# ArduinoMicroFullCustom.net
KiCad netlist of a schematic drawn in EAGLE
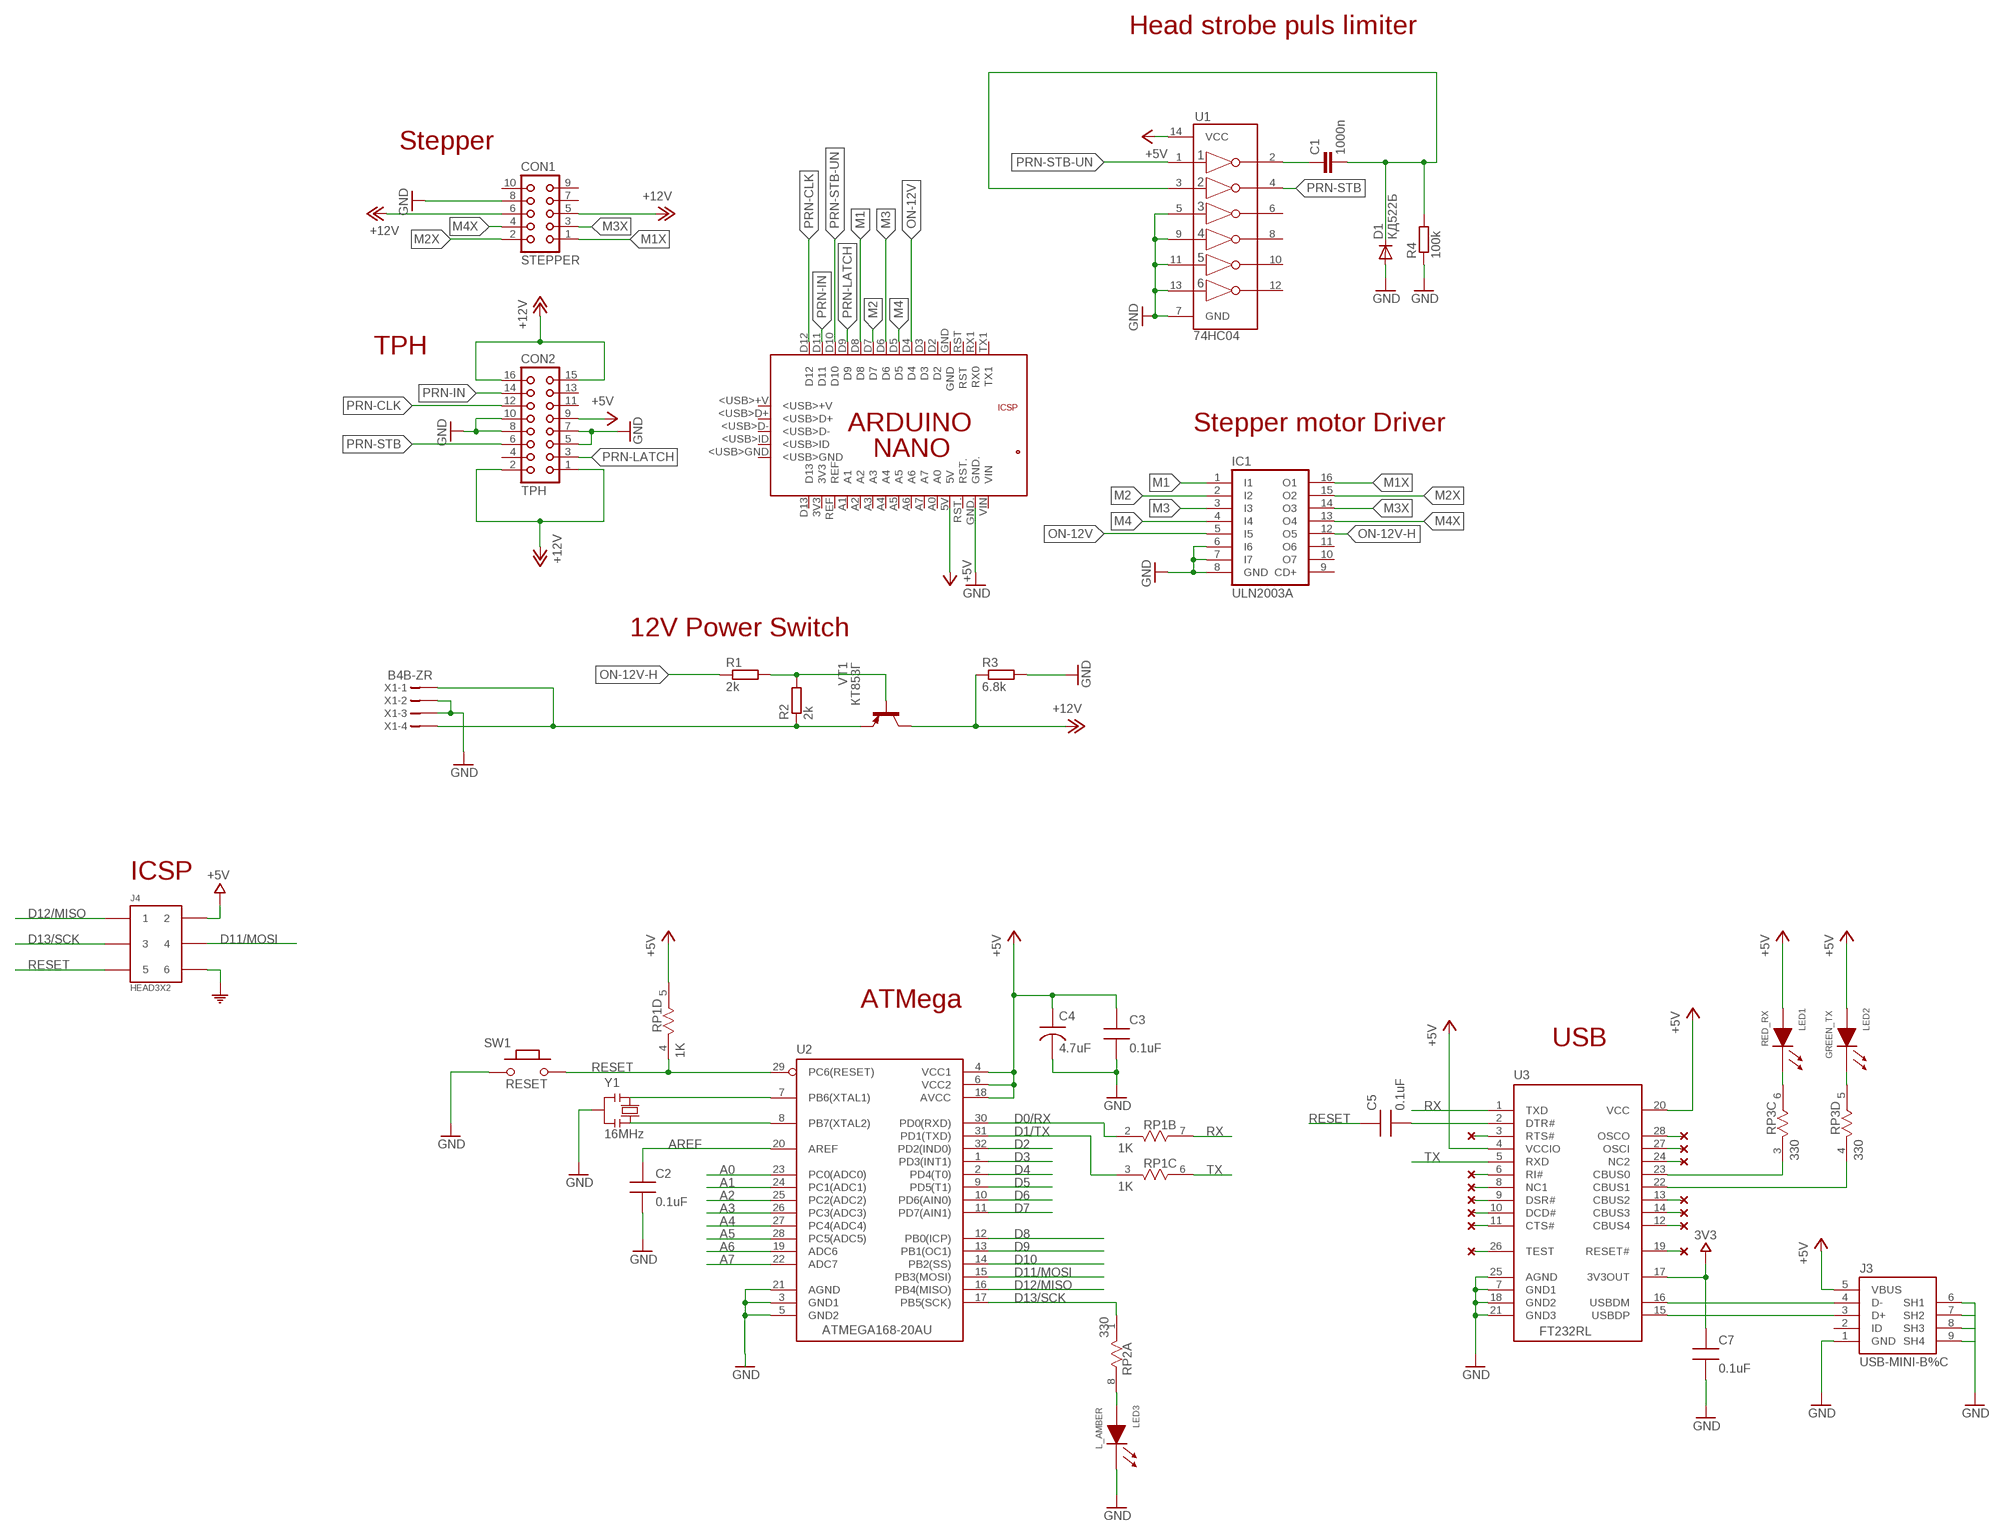
[diagram p0: schematic, sheet 1]

(export (version "E")
  (design (tool "Eeschema 10.0.6"))
  (components
    (comp (ref "C1")
      (value "1000n")
      (footprint "eagle-import:C075-032X103")
      (libsource (lib "eagle-import") (part "C-EU075-032X103"))
    )
    (comp (ref "C2")
      (value "0.1uF")
      (footprint "eagle-import:CAP0805-NP")
      (libsource (lib "eagle-import") (part "CAP0805-NP"))
    )
    (comp (ref "C3")
      (value "0.1uF")
      (footprint "eagle-import:CAP0805-NP")
      (libsource (lib "eagle-import") (part "CAP0805-NP"))
    )
    (comp (ref "C4")
      (value "4.7uF")
      (footprint "eagle-import:TAN-A")
      (libsource (lib "eagle-import") (part "CAP-TANA-P"))
    )
    (comp (ref "C5")
      (value "0.1uF")
      (footprint "eagle-import:CAP0805-NP")
      (libsource (lib "eagle-import") (part "CAP0805-NP"))
    )
    (comp (ref "C7")
      (value "0.1uF")
      (footprint "eagle-import:CAP0805-NP")
      (libsource (lib "eagle-import") (part "CAP0805-NP"))
    )
    (comp (ref "CON1")
      (value "STEPPER")
      (footprint "eagle-import:CON10")
      (fields
        (field (name "MF") "TE CONNECTIVITY / AMP")
        (field (name "MPN") "0-281273-1")
        (field (name "OC_FARNELL") "3816278")
      )
      (libsource (lib "eagle-import") (part "CON10"))
    )
    (comp (ref "CON2")
      (value "TPH")
      (footprint "eagle-import:CON16")
      (fields
        (field (name "MF") "TE CONNECTIVITY / AMP")
        (field (name "MPN") "1-1634688-0")
        (field (name "OC_FARNELL") "8395918")
      )
      (libsource (lib "eagle-import") (part "CON16"))
    )
    (comp (ref "D1")
      (value "КД522Б")
      (footprint "eagle-import:DO35-10")
      (libsource (lib "eagle-import") (part "1N4148DO35-10"))
    )
    (comp (ref "IC1")
      (value "ULN2003A")
      (footprint "eagle-import:DIL16")
      (libsource (lib "eagle-import") (part "ULN2003AN"))
    )
    (comp (ref "J3")
      (value "USB-MINI-B%C")
      (footprint "eagle-import:USB-MINI-B_2")
      (libsource (lib "eagle-import") (part "USB-MINI-B%C"))
    )
    (comp (ref "J4")
      (value "HEAD3X2")
      (footprint "eagle-import:HEAD3X2")
      (libsource (lib "eagle-import") (part "HEAD3X2"))
    )
    (comp (ref "LED1")
      (value "RED_RX")
      (footprint "eagle-import:LED0805")
      (libsource (lib "eagle-import") (part "LED0805"))
    )
    (comp (ref "LED2")
      (value "GREEN_TX")
      (footprint "eagle-import:LED0805")
      (libsource (lib "eagle-import") (part "LED0805"))
    )
    (comp (ref "LED3")
      (value "L_AMBER")
      (footprint "eagle-import:LED0805")
      (libsource (lib "eagle-import") (part "LED0805"))
    )
    (comp (ref "PCB1")
      (value "ARDUINO_NANO")
      (footprint "eagle-import:ARDUINO_NANO")
      (fields (field (name "MF") "ARDUINO") (field (name "MPN") "A000005"))
      (libsource (lib "eagle-import") (part "ARDUINO_NANO"))
    )
    (comp (ref "R1")
      (value "2k")
      (footprint "eagle-import:0207_12")
      (libsource (lib "eagle-import") (part "R-EU_0207/12"))
    )
    (comp (ref "R2")
      (value "2k")
      (footprint "eagle-import:0207_12")
      (libsource (lib "eagle-import") (part "R-EU_0207/12"))
    )
    (comp (ref "R3")
      (value "6.8k")
      (footprint "eagle-import:0207_12")
      (libsource (lib "eagle-import") (part "R-EU_0207/12"))
    )
    (comp (ref "R4")
      (value "100k")
      (footprint "eagle-import:0309_12")
      (libsource (lib "eagle-import") (part "R-EU_0309/12"))
    )
    (comp (ref "RP1")
      (value "1K")
      (footprint "eagle-import:RES4NT")
      (libsource (lib "eagle-import") (part "RES4NT"))
    )
    (comp (ref "RP2")
      (value "330")
      (footprint "eagle-import:RES4NT")
      (libsource (lib "eagle-import") (part "RES4NT"))
    )
    (comp (ref "RP3")
      (value "330")
      (footprint "eagle-import:RES4NT")
      (libsource (lib "eagle-import") (part "RES4NT"))
    )
    (comp (ref "SW1")
      (value "RESET")
      (footprint "eagle-import:157SW")
      (libsource (lib "eagle-import") (part "PB157"))
    )
    (comp (ref "U1")
      (value "74HC04")
      (footprint "eagle-import:DIL14")
      (libsource (lib "eagle-import") (part "74HC04_HEX_INVERTER"))
    )
    (comp (ref "U2")
      (value "ATMEGA168-20AU")
      (footprint "eagle-import:QFP032")
      (libsource (lib "eagle-import") (part "ATMEGA168-20AU"))
    )
    (comp (ref "U3")
      (value "FT232RL")
      (footprint "eagle-import:SSOP28")
      (libsource (lib "eagle-import") (part "FT232RL"))
    )
    (comp (ref "VT1")
      (value "КТ853Г")
      (footprint "eagle-import:TO220")
      (libsource (lib "eagle-import") (part "TIP30"))
    )
    (comp (ref "X1")
      (value "B4B-ZR")
      (footprint "eagle-import:B4B-ZR")
      (fields (field (name "MF") "FARNELL") (field (name "MPN") "B4B-ZR(LF)(SN)"))
      (libsource (lib "eagle-import") (part "?4B-ZRB"))
    )
    (comp (ref "Y1")
      (value "16MHz")
      (footprint "eagle-import:RESONATOR")
      (libsource (lib "eagle-import") (part "RESONATORMU"))
    )
  )
  (nets
    (net (code "1") (name "+5V") (class "Default")
      (node (ref "C3") (pin "1") (pinfunction "1_1") (pintype "passive"))
      (node (ref "C4") (pin "1") (pinfunction "1_1") (pintype "passive"))
      (node (ref "CON2") (pin "9") (pinfunction "9_9") (pintype "passive"))
      (node (ref "J3") (pin "5") (pinfunction "VBUS_5") (pintype "power_in"))
      (node (ref "J4") (pin "2") (pinfunction "2_2") (pintype "passive"))
      (node (ref "LED1") (pin "2") (pinfunction "AN_2") (pintype "passive"))
      (node (ref "LED2") (pin "2") (pinfunction "AN_2") (pintype "passive"))
      (node (ref "PCB1") (pin "5V") (pinfunction "5V_5V") (pintype "bidirectional"))
      (node (ref "RP1") (pin "5") (pinfunction "2_5") (pintype "passive"))
      (node (ref "U1") (pin "14") (pinfunction "VCC_14") (pintype "power_in"))
      (node (ref "U2") (pin "18") (pinfunction "AVCC_18") (pintype "passive"))
      (node (ref "U2") (pin "4") (pinfunction "VCC1_4") (pintype "power_in"))
      (node (ref "U2") (pin "6") (pinfunction "VCC2_6") (pintype "power_in"))
      (node (ref "U3") (pin "20") (pinfunction "VCC_20") (pintype "power_in"))
      (node (ref "U3") (pin "4") (pinfunction "VCCIO_4") (pintype "power_in"))
    )
    (net (code "2") (name "+12V") (class "Default")
      (node (ref "CON1") (pin "5") (pinfunction "5_5") (pintype "passive"))
      (node (ref "CON1") (pin "6") (pinfunction "6_6") (pintype "passive"))
      (node (ref "CON2") (pin "1") (pinfunction "1_1") (pintype "passive"))
      (node (ref "CON2") (pin "15") (pinfunction "15_15") (pintype "passive"))
      (node (ref "CON2") (pin "16") (pinfunction "16_16") (pintype "passive"))
      (node (ref "CON2") (pin "2") (pinfunction "2_2") (pintype "passive"))
      (node (ref "R3") (pin "1") (pinfunction "1_1") (pintype "passive"))
      (node (ref "VT1") (pin "2") (pinfunction "C_2") (pintype "passive"))
    )
    (net (code "3") (name "/A0") (class "Default")
      (node (ref "U2") (pin "23") (pinfunction "PC0(ADC0)_23") (pintype "passive"))
    )
    (net (code "4") (name "/A1") (class "Default")
      (node (ref "U2") (pin "24") (pinfunction "PC1(ADC1)_24") (pintype "passive"))
    )
    (net (code "5") (name "/A2") (class "Default")
      (node (ref "U2") (pin "25") (pinfunction "PC2(ADC2)_25") (pintype "passive"))
    )
    (net (code "6") (name "/A3") (class "Default")
      (node (ref "U2") (pin "26") (pinfunction "PC3(ADC3)_26") (pintype "passive"))
    )
    (net (code "7") (name "/A4") (class "Default")
      (node (ref "U2") (pin "27") (pinfunction "PC4(ADC4)_27") (pintype "passive"))
    )
    (net (code "8") (name "/A5") (class "Default")
      (node (ref "U2") (pin "28") (pinfunction "PC5(ADC5)_28") (pintype "passive"))
    )
    (net (code "9") (name "/A6") (class "Default")
      (node (ref "U2") (pin "19") (pinfunction "ADC6_19") (pintype "passive"))
    )
    (net (code "10") (name "/A7") (class "Default")
      (node (ref "U2") (pin "22") (pinfunction "ADC7_22") (pintype "passive"))
    )
    (net (code "11") (name "/AREF") (class "Default")
      (node (ref "C2") (pin "1") (pinfunction "1_1") (pintype "passive"))
      (node (ref "U2") (pin "20") (pinfunction "AREF_20") (pintype "passive"))
    )
    (net (code "12") (name "/D0{slash}RX") (class "Default")
      (node (ref "RP1") (pin "2") (pinfunction "1_2") (pintype "passive"))
      (node (ref "U2") (pin "30") (pinfunction "PD0(RXD)_30") (pintype "bidirectional"))
    )
    (net (code "13") (name "/D1{slash}TX") (class "Default")
      (node (ref "RP1") (pin "3") (pinfunction "1_3") (pintype "passive"))
      (node (ref "U2") (pin "31") (pinfunction "PD1(TXD)_31") (pintype "bidirectional"))
    )
    (net (code "14") (name "/D2") (class "Default")
      (node (ref "U2") (pin "32") (pinfunction "PD2(IND0)_32") (pintype "bidirectional"))
    )
    (net (code "15") (name "/D3") (class "Default")
      (node (ref "U2") (pin "1") (pinfunction "PD3(INT1)_1") (pintype "bidirectional"))
    )
    (net (code "16") (name "/D4") (class "Default")
      (node (ref "U2") (pin "2") (pinfunction "PD4(T0)_2") (pintype "bidirectional"))
    )
    (net (code "17") (name "/D5") (class "Default")
      (node (ref "U2") (pin "9") (pinfunction "PD5(T1)_9") (pintype "bidirectional"))
    )
    (net (code "18") (name "/D6") (class "Default")
      (node (ref "U2") (pin "10") (pinfunction "PD6(AIN0)_10") (pintype "bidirectional"))
    )
    (net (code "19") (name "/D7") (class "Default")
      (node (ref "U2") (pin "11") (pinfunction "PD7(AIN1)_11") (pintype "bidirectional"))
    )
    (net (code "20") (name "/D8") (class "Default")
      (node (ref "U2") (pin "12") (pinfunction "PB0(ICP)_12") (pintype "bidirectional"))
    )
    (net (code "21") (name "/D9") (class "Default")
      (node (ref "U2") (pin "13") (pinfunction "PB1(OC1)_13") (pintype "bidirectional"))
    )
    (net (code "22") (name "/D10") (class "Default")
      (node (ref "U2") (pin "14") (pinfunction "PB2(SS)_14") (pintype "bidirectional"))
    )
    (net (code "23") (name "/D11{slash}MOSI") (class "Default")
      (node (ref "J4") (pin "4") (pinfunction "4_4") (pintype "passive"))
      (node (ref "U2") (pin "15") (pinfunction "PB3(MOSI)_15") (pintype "bidirectional"))
    )
    (net (code "24") (name "/D12{slash}MISO") (class "Default")
      (node (ref "J4") (pin "1") (pinfunction "1_1") (pintype "passive"))
      (node (ref "U2") (pin "16") (pinfunction "PB4(MISO)_16") (pintype "bidirectional"))
    )
    (net (code "25") (name "/D13{slash}SCK") (class "Default")
      (node (ref "J4") (pin "3") (pinfunction "3_3") (pintype "passive"))
      (node (ref "RP2") (pin "1") (pinfunction "1_1") (pintype "passive"))
      (node (ref "U2") (pin "17") (pinfunction "PB5(SCK)_17") (pintype "bidirectional"))
    )
    (net (code "26") (name "/RESET") (class "Default")
      (node (ref "C5") (pin "1") (pinfunction "1_1") (pintype "passive"))
      (node (ref "J4") (pin "5") (pinfunction "5_5") (pintype "passive"))
      (node (ref "RP1") (pin "4") (pinfunction "1_4") (pintype "passive"))
      (node (ref "SW1") (pin "2") (pinfunction "2_2") (pintype "passive"))
      (node (ref "U2") (pin "29") (pinfunction "PC6(RESET)_29") (pintype "bidirectional"))
    )
    (net (code "27") (name "/RX") (class "Default")
      (node (ref "RP1") (pin "7") (pinfunction "2_7") (pintype "passive"))
      (node (ref "U3") (pin "1") (pinfunction "TXD_1") (pintype "output"))
    )
    (net (code "28") (name "/TX") (class "Default")
      (node (ref "RP1") (pin "6") (pinfunction "2_6") (pintype "passive"))
      (node (ref "U3") (pin "5") (pinfunction "RXD_5") (pintype "input"))
    )
    (net (code "29") (name "3V3") (class "Default")
      (node (ref "C7") (pin "1") (pinfunction "1_1") (pintype "passive"))
      (node (ref "U3") (pin "17") (pinfunction "3V3OUT_17") (pintype "power_in"))
    )
    (net (code "30") (name "COM") (class "Default")
      (node (ref "J4") (pin "6") (pinfunction "6_6") (pintype "passive"))
    )
    (net (code "31") (name "GND") (class "Default")
      (node (ref "C2") (pin "2") (pinfunction "2_2") (pintype "passive"))
      (node (ref "C3") (pin "2") (pinfunction "2_2") (pintype "passive"))
      (node (ref "C4") (pin "2") (pinfunction "2_2") (pintype "passive"))
      (node (ref "C7") (pin "2") (pinfunction "2_2") (pintype "passive"))
      (node (ref "CON1") (pin "8") (pinfunction "8_8") (pintype "passive"))
      (node (ref "CON2") (pin "10") (pinfunction "10_10") (pintype "passive"))
      (node (ref "CON2") (pin "5") (pinfunction "5_5") (pintype "passive"))
      (node (ref "CON2") (pin "7") (pinfunction "7_7") (pintype "passive"))
      (node (ref "CON2") (pin "8") (pinfunction "8_8") (pintype "passive"))
      (node (ref "D1") (pin "A") (pinfunction "A_A") (pintype "passive"))
      (node (ref "IC1") (pin "6") (pinfunction "I6_6") (pintype "input"))
      (node (ref "IC1") (pin "7") (pinfunction "I7_7") (pintype "input"))
      (node (ref "IC1") (pin "8") (pinfunction "GND_8") (pintype "power_in"))
      (node (ref "J3") (pin "1") (pinfunction "GND_1") (pintype "passive"))
      (node (ref "J3") (pin "6") (pinfunction "SH1_6") (pintype "passive"))
      (node (ref "J3") (pin "7") (pinfunction "SH2_7") (pintype "passive"))
      (node (ref "J3") (pin "8") (pinfunction "SH3_8") (pintype "passive"))
      (node (ref "J3") (pin "9") (pinfunction "SH4_9") (pintype "passive"))
      (node (ref "LED3") (pin "1") (pinfunction "CA_1") (pintype "passive"))
      (node (ref "PCB1") (pin "GND.") (pinfunction "GND._GND.") (pintype "bidirectional"))
      (node (ref "R3") (pin "2") (pinfunction "2_2") (pintype "passive"))
      (node (ref "R4") (pin "1") (pinfunction "1_1") (pintype "passive"))
      (node (ref "SW1") (pin "1") (pinfunction "1_1") (pintype "passive"))
      (node (ref "U1") (pin "11") (pinfunction "5A_11") (pintype "input"))
      (node (ref "U1") (pin "13") (pinfunction "6A_13") (pintype "input"))
      (node (ref "U1") (pin "5") (pinfunction "3A_5") (pintype "input"))
      (node (ref "U1") (pin "7") (pinfunction "GND_7") (pintype "power_in"))
      (node (ref "U1") (pin "9") (pinfunction "4A_9") (pintype "input"))
      (node (ref "U2") (pin "21") (pinfunction "AGND_21") (pintype "passive"))
      (node (ref "U2") (pin "3") (pinfunction "GND1_3") (pintype "power_in"))
      (node (ref "U2") (pin "5") (pinfunction "GND2_5") (pintype "power_in"))
      (node (ref "U3") (pin "18") (pinfunction "GND2_18") (pintype "power_in"))
      (node (ref "U3") (pin "21") (pinfunction "GND3_21") (pintype "power_in"))
      (node (ref "U3") (pin "25") (pinfunction "AGND_25") (pintype "power_in"))
      (node (ref "U3") (pin "7") (pinfunction "GND1_7") (pintype "power_in"))
      (node (ref "X1") (pin "2") (pinfunction "1_2") (pintype "passive"))
      (node (ref "X1") (pin "3") (pinfunction "1_3") (pintype "passive"))
      (node (ref "Y1") (pin "2") (pinfunction "2_2") (pintype "passive"))
    )
    (net (code "32") (name "M1") (class "Default")
      (node (ref "IC1") (pin "1") (pinfunction "I1_1") (pintype "input"))
      (node (ref "PCB1") (pin "D8") (pinfunction "D8_D8") (pintype "bidirectional"))
    )
    (net (code "33") (name "M1X") (class "Default")
      (node (ref "CON1") (pin "1") (pinfunction "1_1") (pintype "passive"))
      (node (ref "IC1") (pin "16") (pinfunction "O1_16") (pintype "open_collector"))
    )
    (net (code "34") (name "M2") (class "Default")
      (node (ref "IC1") (pin "2") (pinfunction "I2_2") (pintype "input"))
      (node (ref "PCB1") (pin "D7") (pinfunction "D7_D7") (pintype "bidirectional"))
    )
    (net (code "35") (name "M2X") (class "Default")
      (node (ref "CON1") (pin "2") (pinfunction "2_2") (pintype "passive"))
      (node (ref "IC1") (pin "15") (pinfunction "O2_15") (pintype "open_collector"))
    )
    (net (code "36") (name "M3") (class "Default")
      (node (ref "IC1") (pin "3") (pinfunction "I3_3") (pintype "input"))
      (node (ref "PCB1") (pin "D6") (pinfunction "D6_D6") (pintype "bidirectional"))
    )
    (net (code "37") (name "M3X") (class "Default")
      (node (ref "CON1") (pin "3") (pinfunction "3_3") (pintype "passive"))
      (node (ref "IC1") (pin "14") (pinfunction "O3_14") (pintype "open_collector"))
    )
    (net (code "38") (name "M4") (class "Default")
      (node (ref "IC1") (pin "4") (pinfunction "I4_4") (pintype "input"))
      (node (ref "PCB1") (pin "D5") (pinfunction "D5_D5") (pintype "bidirectional"))
    )
    (net (code "39") (name "M4X") (class "Default")
      (node (ref "CON1") (pin "4") (pinfunction "4_4") (pintype "passive"))
      (node (ref "IC1") (pin "13") (pinfunction "O4_13") (pintype "open_collector"))
    )
    (net (code "40") (name "Net-(J3-D+)") (class "Default")
      (node (ref "J3") (pin "3") (pinfunction "D+_3") (pintype "bidirectional"))
      (node (ref "U3") (pin "15") (pinfunction "USBDP_15") (pintype "bidirectional"))
    )
    (net (code "41") (name "Net-(J3-D-)") (class "Default")
      (node (ref "J3") (pin "4") (pinfunction "D-_4") (pintype "bidirectional"))
      (node (ref "U3") (pin "16") (pinfunction "USBDM_16") (pintype "bidirectional"))
    )
    (net (code "42") (name "Net-(LED1-CA)") (class "Default")
      (node (ref "LED1") (pin "1") (pinfunction "CA_1") (pintype "passive"))
      (node (ref "RP3") (pin "6") (pinfunction "2_6") (pintype "passive"))
    )
    (net (code "43") (name "Net-(LED2-CA)") (class "Default")
      (node (ref "LED2") (pin "1") (pinfunction "CA_1") (pintype "passive"))
      (node (ref "RP3") (pin "5") (pinfunction "2_5") (pintype "passive"))
    )
    (net (code "44") (name "Net-(LED3-AN)") (class "Default")
      (node (ref "LED3") (pin "2") (pinfunction "AN_2") (pintype "passive"))
      (node (ref "RP2") (pin "8") (pinfunction "2_8") (pintype "passive"))
    )
    (net (code "45") (name "Net-(RP3C-1)") (class "Default")
      (node (ref "RP3") (pin "3") (pinfunction "1_3") (pintype "passive"))
      (node (ref "U3") (pin "23") (pinfunction "CBUS0_23") (pintype "bidirectional"))
    )
    (net (code "46") (name "Net-(RP3D-1)") (class "Default")
      (node (ref "RP3") (pin "4") (pinfunction "1_4") (pintype "passive"))
      (node (ref "U3") (pin "22") (pinfunction "CBUS1_22") (pintype "bidirectional"))
    )
    (net (code "47") (name "Net-(U1-1Y)") (class "Default")
      (node (ref "C1") (pin "1") (pinfunction "1_1") (pintype "passive"))
      (node (ref "U1") (pin "2") (pinfunction "1Y_2") (pintype "output"))
    )
    (net (code "48") (name "Net-(U1-2A)") (class "Default")
      (node (ref "C1") (pin "2") (pinfunction "2_2") (pintype "passive"))
      (node (ref "D1") (pin "C") (pinfunction "C_C") (pintype "passive"))
      (node (ref "R4") (pin "2") (pinfunction "2_2") (pintype "passive"))
      (node (ref "U1") (pin "3") (pinfunction "2A_3") (pintype "input"))
    )
    (net (code "49") (name "Net-(U2-PB6(XTAL1))") (class "Default")
      (node (ref "U2") (pin "7") (pinfunction "PB6(XTAL1)_7") (pintype "passive"))
      (node (ref "Y1") (pin "1") (pinfunction "1_1") (pintype "passive"))
    )
    (net (code "50") (name "Net-(U2-PB7(XTAL2))") (class "Default")
      (node (ref "U2") (pin "8") (pinfunction "PB7(XTAL2)_8") (pintype "passive"))
      (node (ref "Y1") (pin "3") (pinfunction "3_3") (pintype "passive"))
    )
    (net (code "51") (name "Net-(U3-DTR#)") (class "Default")
      (node (ref "C5") (pin "2") (pinfunction "2_2") (pintype "passive"))
      (node (ref "U3") (pin "2") (pinfunction "DTR#_2") (pintype "output"))
    )
    (net (code "52") (name "Net-(VT1-B)") (class "Default")
      (node (ref "R1") (pin "2") (pinfunction "2_2") (pintype "passive"))
      (node (ref "R2") (pin "2") (pinfunction "2_2") (pintype "passive"))
      (node (ref "VT1") (pin "1") (pinfunction "B_1") (pintype "passive"))
    )
    (net (code "53") (name "Net-(VT1-E)") (class "Default")
      (node (ref "R2") (pin "1") (pinfunction "1_1") (pintype "passive"))
      (node (ref "VT1") (pin "3") (pinfunction "E_3") (pintype "passive"))
      (node (ref "X1") (pin "1") (pinfunction "1_1") (pintype "passive"))
      (node (ref "X1") (pin "4") (pinfunction "1_4") (pintype "passive"))
    )
    (net (code "54") (name "ON-12V") (class "Default")
      (node (ref "IC1") (pin "5") (pinfunction "I5_5") (pintype "input"))
      (node (ref "PCB1") (pin "D4") (pinfunction "D4_D4") (pintype "bidirectional"))
    )
    (net (code "55") (name "ON-12V-H") (class "Default")
      (node (ref "IC1") (pin "12") (pinfunction "O5_12") (pintype "open_collector"))
      (node (ref "R1") (pin "1") (pinfunction "1_1") (pintype "passive"))
    )
    (net (code "56") (name "PRN-CLK") (class "Default")
      (node (ref "CON2") (pin "12") (pinfunction "12_12") (pintype "passive"))
      (node (ref "PCB1") (pin "D12") (pinfunction "D12_D12") (pintype "bidirectional"))
    )
    (net (code "57") (name "PRN-IN") (class "Default")
      (node (ref "CON2") (pin "14") (pinfunction "14_14") (pintype "passive"))
      (node (ref "PCB1") (pin "D11") (pinfunction "D11_D11") (pintype "bidirectional"))
    )
    (net (code "58") (name "PRN-LATCH") (class "Default")
      (node (ref "CON2") (pin "3") (pinfunction "3_3") (pintype "passive"))
      (node (ref "PCB1") (pin "D9") (pinfunction "D9_D9") (pintype "bidirectional"))
    )
    (net (code "59") (name "PRN-STB") (class "Default")
      (node (ref "CON2") (pin "6") (pinfunction "6_6") (pintype "passive"))
      (node (ref "U1") (pin "4") (pinfunction "2Y_4") (pintype "output"))
    )
    (net (code "60") (name "PRN-STB-UN") (class "Default")
      (node (ref "PCB1") (pin "D10") (pinfunction "D10_D10") (pintype "bidirectional"))
      (node (ref "U1") (pin "1") (pinfunction "1A_1") (pintype "input"))
    )
    (net (code "61") (name "unconnected-(CON1-Pad7)") (class "Default")
      (node (ref "CON1") (pin "7") (pinfunction "7_7") (pintype "passive"))
    )
    (net (code "62") (name "unconnected-(CON1-Pad9)") (class "Default")
      (node (ref "CON1") (pin "9") (pinfunction "9_9") (pintype "passive"))
    )
    (net (code "63") (name "unconnected-(CON1-Pad10)") (class "Default")
      (node (ref "CON1") (pin "10") (pinfunction "10_10") (pintype "passive"))
    )
    (net (code "64") (name "unconnected-(CON2-Pad4)") (class "Default")
      (node (ref "CON2") (pin "4") (pinfunction "4_4") (pintype "passive"))
    )
    (net (code "65") (name "unconnected-(CON2-Pad11)") (class "Default")
      (node (ref "CON2") (pin "11") (pinfunction "11_11") (pintype "passive"))
    )
    (net (code "66") (name "unconnected-(CON2-Pad13)") (class "Default")
      (node (ref "CON2") (pin "13") (pinfunction "13_13") (pintype "passive"))
    )
    (net (code "67") (name "unconnected-(IC1-CD+-Pad9)") (class "Default")
      (node (ref "IC1") (pin "9") (pinfunction "CD+_9") (pintype "passive"))
    )
    (net (code "68") (name "unconnected-(IC1-O6-Pad11)") (class "Default")
      (node (ref "IC1") (pin "11") (pinfunction "O6_11") (pintype "open_collector"))
    )
    (net (code "69") (name "unconnected-(IC1-O7-Pad10)") (class "Default")
      (node (ref "IC1") (pin "10") (pinfunction "O7_10") (pintype "open_collector"))
    )
    (net (code "70") (name "unconnected-(J3-ID-Pad2)") (class "Default")
      (node (ref "J3") (pin "2") (pinfunction "ID_2") (pintype "bidirectional"))
    )
    (net (code "71") (name "unconnected-(PCB1-Pad3V3)") (class "Default")
      (node (ref "PCB1") (pin "3V3") (pinfunction "3V3_3V3") (pintype "bidirectional"))
    )
    (net (code "72") (name "unconnected-(PCB1-Pad5V.)") (class "Default")
      (node (ref "PCB1") (pin "5V.") (pinfunction "5V._5V.") (pintype "bidirectional"))
    )
    (net (code "73") (name "unconnected-(PCB1-Pad<USB>+V)") (class "Default")
      (node (ref "PCB1") (pin "<USB>+V") (pinfunction "<USB>+V_<USB>+V") (pintype "bidirectional"))
    )
    (net (code "74") (name "unconnected-(PCB1-Pad<USB>D+)") (class "Default")
      (node (ref "PCB1") (pin "<USB>D+") (pinfunction "<USB>D+_<USB>D+") (pintype "bidirectional"))
    )
    (net (code "75") (name "unconnected-(PCB1-Pad<USB>D-)") (class "Default")
      (node (ref "PCB1") (pin "<USB>D-") (pinfunction "<USB>D-_<USB>D-") (pintype "bidirectional"))
    )
    (net (code "76") (name "unconnected-(PCB1-Pad<USB>GND)") (class "Default")
      (node (ref "PCB1") (pin "<USB>GND") (pinfunction "<USB>GND_<USB>GND") (pintype "bidirectional"))
    )
    (net (code "77") (name "unconnected-(PCB1-Pad<USB>ID)") (class "Default")
      (node (ref "PCB1") (pin "<USB>ID") (pinfunction "<USB>ID_<USB>ID") (pintype "bidirectional"))
    )
    (net (code "78") (name "unconnected-(PCB1-PadA0)") (class "Default")
      (node (ref "PCB1") (pin "A0") (pinfunction "A0_A0") (pintype "bidirectional"))
    )
    (net (code "79") (name "unconnected-(PCB1-PadA1)") (class "Default")
      (node (ref "PCB1") (pin "A1") (pinfunction "A1_A1") (pintype "bidirectional"))
    )
    (net (code "80") (name "unconnected-(PCB1-PadA2)") (class "Default")
      (node (ref "PCB1") (pin "A2") (pinfunction "A2_A2") (pintype "bidirectional"))
    )
    (net (code "81") (name "unconnected-(PCB1-PadA3)") (class "Default")
      (node (ref "PCB1") (pin "A3") (pinfunction "A3_A3") (pintype "bidirectional"))
    )
    (net (code "82") (name "unconnected-(PCB1-PadA4)") (class "Default")
      (node (ref "PCB1") (pin "A4") (pinfunction "A4_A4") (pintype "bidirectional"))
    )
    (net (code "83") (name "unconnected-(PCB1-PadA5)") (class "Default")
      (node (ref "PCB1") (pin "A5") (pinfunction "A5_A5") (pintype "bidirectional"))
    )
    (net (code "84") (name "unconnected-(PCB1-PadA6)") (class "Default")
      (node (ref "PCB1") (pin "A6") (pinfunction "A6_A6") (pintype "bidirectional"))
    )
    (net (code "85") (name "unconnected-(PCB1-PadA7)") (class "Default")
      (node (ref "PCB1") (pin "A7") (pinfunction "A7_A7") (pintype "bidirectional"))
    )
    (net (code "86") (name "unconnected-(PCB1-PadD2)") (class "Default")
      (node (ref "PCB1") (pin "D2") (pinfunction "D2_D2") (pintype "bidirectional"))
    )
    (net (code "87") (name "unconnected-(PCB1-PadD3)") (class "Default")
      (node (ref "PCB1") (pin "D3") (pinfunction "D3_D3") (pintype "bidirectional"))
    )
    (net (code "88") (name "unconnected-(PCB1-PadD13)") (class "Default")
      (node (ref "PCB1") (pin "D13") (pinfunction "D13_D13") (pintype "bidirectional"))
    )
    (net (code "89") (name "unconnected-(PCB1-PadGND)") (class "Default")
      (node (ref "PCB1") (pin "GND") (pinfunction "GND_GND") (pintype "bidirectional"))
    )
    (net (code "90") (name "unconnected-(PCB1-PadGND_)") (class "Default")
      (node (ref "PCB1") (pin "GND_") (pinfunction "GND__GND_") (pintype "bidirectional"))
    )
    (net (code "91") (name "unconnected-(PCB1-PadMISO)") (class "Default")
      (node (ref "PCB1") (pin "MISO") (pinfunction "MISO_MISO") (pintype "bidirectional"))
    )
    (net (code "92") (name "unconnected-(PCB1-PadMOSI)") (class "Default")
      (node (ref "PCB1") (pin "MOSI") (pinfunction "MOSI_MOSI") (pintype "bidirectional"))
    )
    (net (code "93") (name "unconnected-(PCB1-PadREF)") (class "Default")
      (node (ref "PCB1") (pin "REF") (pinfunction "REF_REF") (pintype "bidirectional"))
    )
    (net (code "94") (name "unconnected-(PCB1-PadRESET..)") (class "Default")
      (node (ref "PCB1") (pin "RESET..") (pinfunction "RESET.._RESET..") (pintype "bidirectional"))
    )
    (net (code "95") (name "unconnected-(PCB1-PadRST)") (class "Default")
      (node (ref "PCB1") (pin "RST") (pinfunction "RST_RST") (pintype "bidirectional"))
    )
    (net (code "96") (name "unconnected-(PCB1-PadRST.)") (class "Default")
      (node (ref "PCB1") (pin "RST.") (pinfunction "RST._RST.") (pintype "bidirectional"))
    )
    (net (code "97") (name "unconnected-(PCB1-PadSCK)") (class "Default")
      (node (ref "PCB1") (pin "SCK") (pinfunction "SCK_SCK") (pintype "bidirectional"))
    )
    (net (code "98") (name "unconnected-(PCB1-PadTX1)") (class "Default")
      (node (ref "PCB1") (pin "TX1") (pinfunction "TX1_TX1") (pintype "bidirectional"))
    )
    (net (code "99") (name "unconnected-(PCB1-PadVIN)") (class "Default")
      (node (ref "PCB1") (pin "VIN") (pinfunction "VIN_VIN") (pintype "bidirectional"))
    )
    (net (code "100") (name "unconnected-(PCB1-RX0-PadRX1)") (class "Default")
      (node (ref "PCB1") (pin "RX1") (pinfunction "RX0_RX1") (pintype "bidirectional"))
    )
    (net (code "101") (name "unconnected-(U1-3Y-Pad6)") (class "Default")
      (node (ref "U1") (pin "6") (pinfunction "3Y_6") (pintype "output"))
    )
    (net (code "102") (name "unconnected-(U1-4Y-Pad8)") (class "Default")
      (node (ref "U1") (pin "8") (pinfunction "4Y_8") (pintype "output"))
    )
    (net (code "103") (name "unconnected-(U1-5Y-Pad10)") (class "Default")
      (node (ref "U1") (pin "10") (pinfunction "5Y_10") (pintype "output"))
    )
    (net (code "104") (name "unconnected-(U1-6Y-Pad12)") (class "Default")
      (node (ref "U1") (pin "12") (pinfunction "6Y_12") (pintype "output"))
    )
    (net (code "105") (name "unconnected-(U3-CBUS2-Pad13)") (class "Default")
      (node (ref "U3") (pin "13") (pinfunction "CBUS2_13") (pintype "bidirectional"))
    )
    (net (code "106") (name "unconnected-(U3-CBUS3-Pad14)") (class "Default")
      (node (ref "U3") (pin "14") (pinfunction "CBUS3_14") (pintype "bidirectional"))
    )
    (net (code "107") (name "unconnected-(U3-CBUS4-Pad12)") (class "Default")
      (node (ref "U3") (pin "12") (pinfunction "CBUS4_12") (pintype "bidirectional"))
    )
    (net (code "108") (name "unconnected-(U3-CTS#-Pad11)") (class "Default")
      (node (ref "U3") (pin "11") (pinfunction "CTS#_11") (pintype "input"))
    )
    (net (code "109") (name "unconnected-(U3-DCD#-Pad10)") (class "Default")
      (node (ref "U3") (pin "10") (pinfunction "DCD#_10") (pintype "input"))
    )
    (net (code "110") (name "unconnected-(U3-DSR#-Pad9)") (class "Default")
      (node (ref "U3") (pin "9") (pinfunction "DSR#_9") (pintype "input"))
    )
    (net (code "111") (name "unconnected-(U3-NC1-Pad8)") (class "Default")
      (node (ref "U3") (pin "8") (pinfunction "NC1_8") (pintype "no_connect"))
    )
    (net (code "112") (name "unconnected-(U3-NC2-Pad24)") (class "Default")
      (node (ref "U3") (pin "24") (pinfunction "NC2_24") (pintype "no_connect"))
    )
    (net (code "113") (name "unconnected-(U3-OSCI-Pad27)") (class "Default")
      (node (ref "U3") (pin "27") (pinfunction "OSCI_27") (pintype "input"))
    )
    (net (code "114") (name "unconnected-(U3-OSCO-Pad28)") (class "Default")
      (node (ref "U3") (pin "28") (pinfunction "OSCO_28") (pintype "output"))
    )
    (net (code "115") (name "unconnected-(U3-RESET#-Pad19)") (class "Default")
      (node (ref "U3") (pin "19") (pinfunction "RESET#_19") (pintype "input"))
    )
    (net (code "116") (name "unconnected-(U3-RI#-Pad6)") (class "Default")
      (node (ref "U3") (pin "6") (pinfunction "RI#_6") (pintype "input"))
    )
    (net (code "117") (name "unconnected-(U3-RTS#-Pad3)") (class "Default")
      (node (ref "U3") (pin "3") (pinfunction "RTS#_3") (pintype "output"))
    )
    (net (code "118") (name "unconnected-(U3-TEST-Pad26)") (class "Default")
      (node (ref "U3") (pin "26") (pinfunction "TEST_26") (pintype "input"))
    )
  )
)
